# untitled.net
KiCad netlist of a schematic drawn in EAGLE
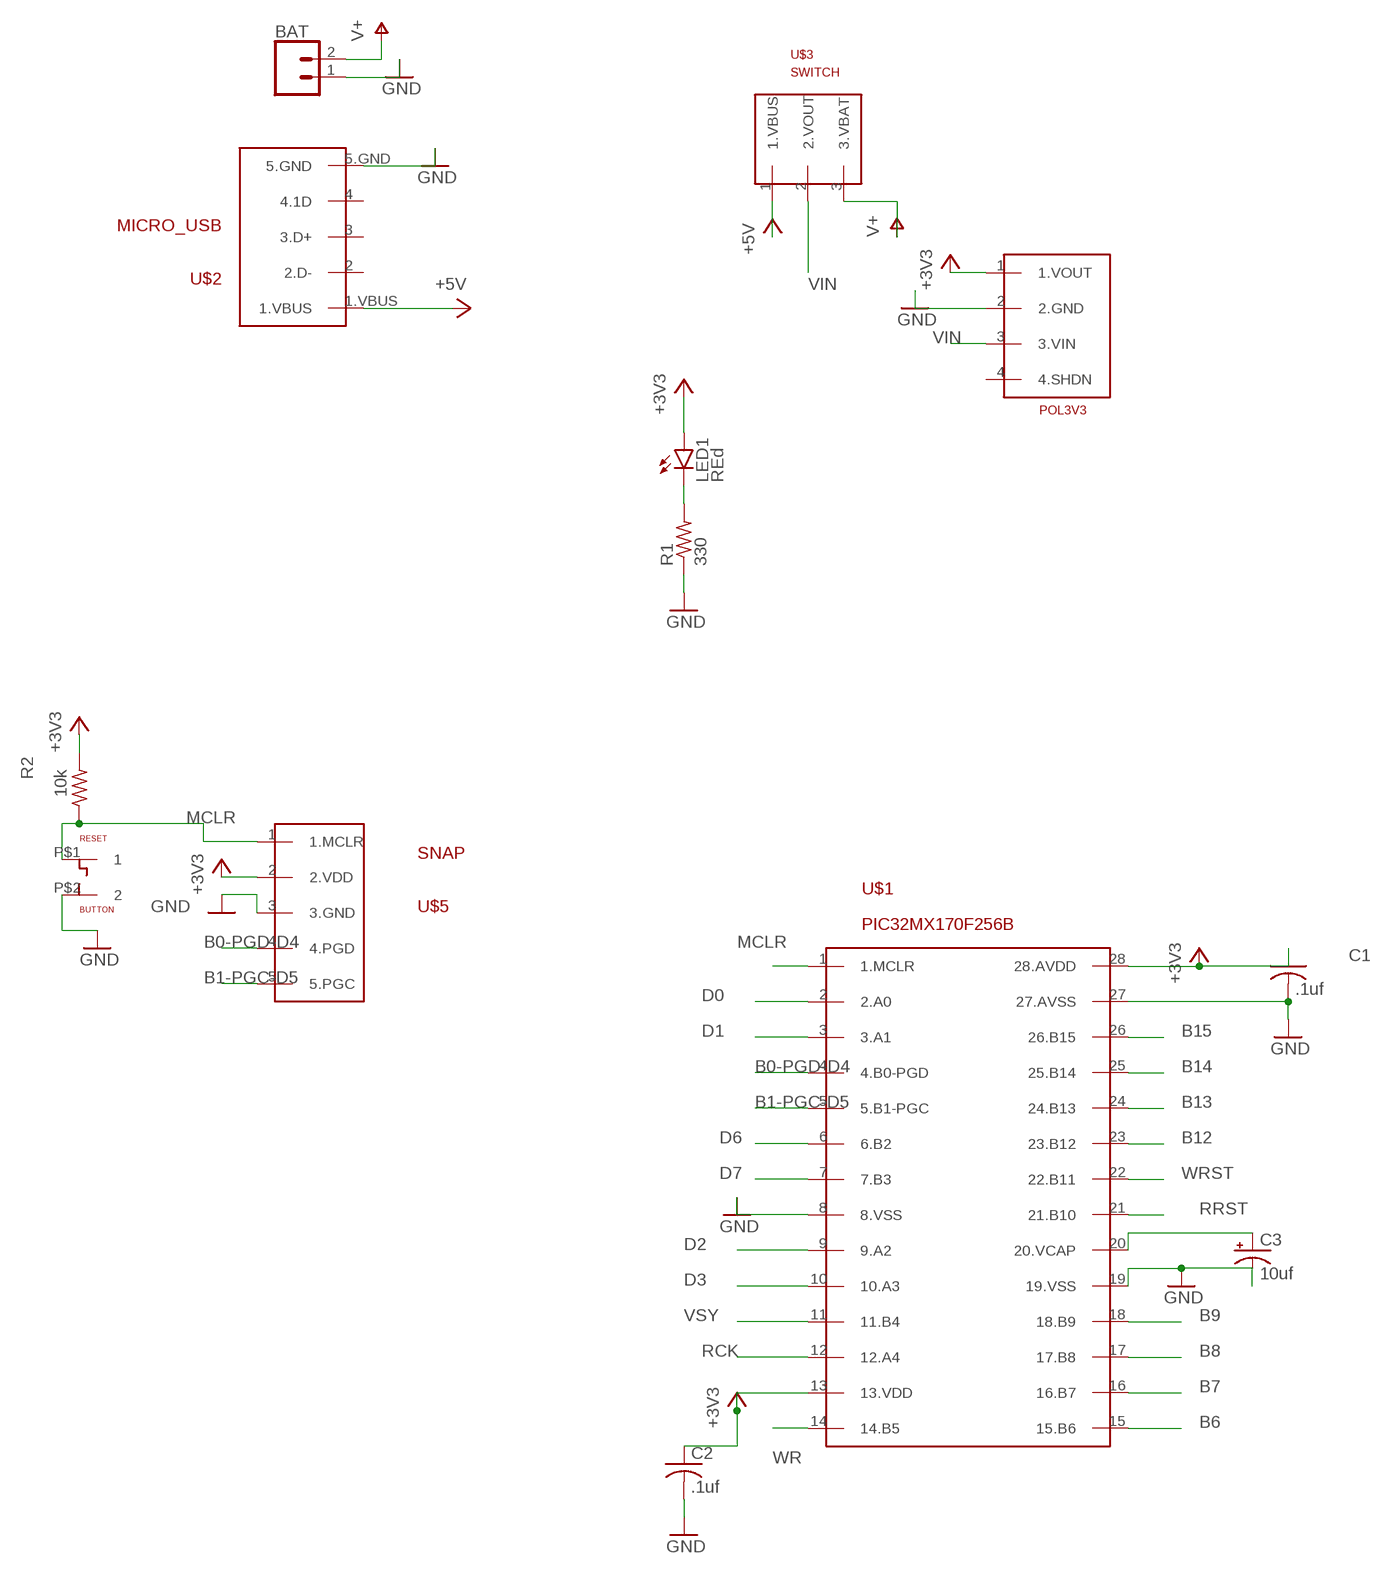
[diagram p0: schematic, sheet 1, part 1 of 2]
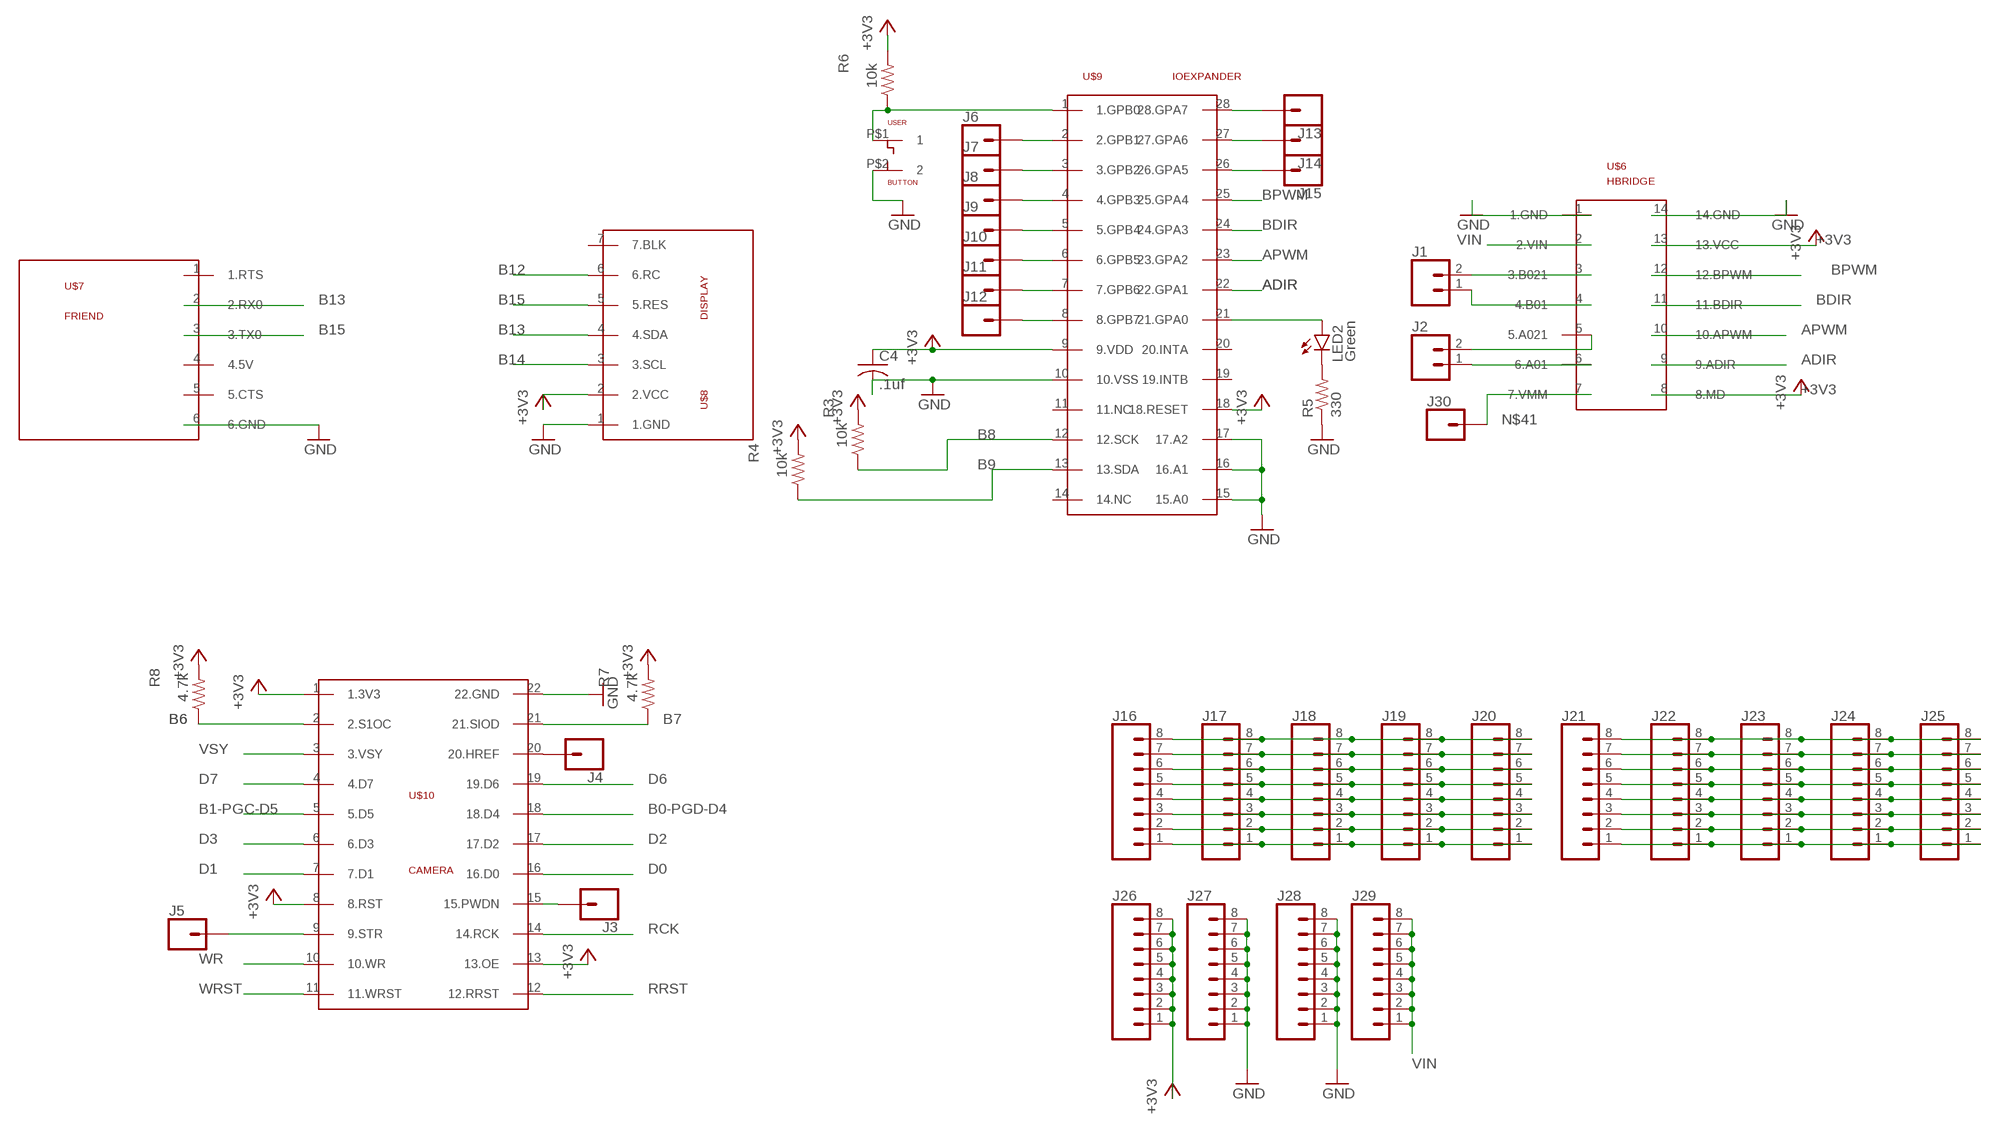
[diagram p1: schematic, sheet 1, part 2 of 2]

(export (version "E")
  (design (tool "Eeschema 10.0.6"))
  (components
    (comp (ref "BAT")
      (value "CONN_02")
      (footprint "eagle-import:1X02")
      (libsource (lib "eagle-import") (part "CONN_02"))
    )
    (comp (ref "C1")
      (value ".1uf")
      (footprint "eagle-import:C025-030X050")
      (libsource (lib "eagle-import") (part "C-US025-030X050"))
    )
    (comp (ref "C2")
      (value ".1uf")
      (footprint "eagle-import:C025-030X050")
      (libsource (lib "eagle-import") (part "C-US025-030X050"))
    )
    (comp (ref "C3")
      (value "10uf")
      (footprint "eagle-import:B45181B")
      (libsource (lib "eagle-import") (part "CPOL-USB45181B"))
    )
    (comp (ref "C4")
      (value ".1uf")
      (footprint "eagle-import:C025-030X050")
      (libsource (lib "eagle-import") (part "C-US025-030X050"))
    )
    (comp (ref "J1")
      (value "CONN_02")
      (footprint "eagle-import:1X02")
      (libsource (lib "eagle-import") (part "CONN_02"))
    )
    (comp (ref "J2")
      (value "CONN_02")
      (footprint "eagle-import:1X02")
      (libsource (lib "eagle-import") (part "CONN_02"))
    )
    (comp (ref "J3")
      (value "CONN_01")
      (footprint "eagle-import:1X01")
      (libsource (lib "eagle-import") (part "CONN_01"))
    )
    (comp (ref "J4")
      (value "CONN_01")
      (footprint "eagle-import:1X01")
      (libsource (lib "eagle-import") (part "CONN_01"))
    )
    (comp (ref "J5")
      (value "CONN_01")
      (footprint "eagle-import:1X01")
      (libsource (lib "eagle-import") (part "CONN_01"))
    )
    (comp (ref "J6")
      (value "CONN_01")
      (footprint "eagle-import:1X01")
      (libsource (lib "eagle-import") (part "CONN_01"))
    )
    (comp (ref "J7")
      (value "CONN_01")
      (footprint "eagle-import:1X01")
      (libsource (lib "eagle-import") (part "CONN_01"))
    )
    (comp (ref "J8")
      (value "CONN_01")
      (footprint "eagle-import:1X01")
      (libsource (lib "eagle-import") (part "CONN_01"))
    )
    (comp (ref "J9")
      (value "CONN_01")
      (footprint "eagle-import:1X01")
      (libsource (lib "eagle-import") (part "CONN_01"))
    )
    (comp (ref "J10")
      (value "CONN_01")
      (footprint "eagle-import:1X01")
      (libsource (lib "eagle-import") (part "CONN_01"))
    )
    (comp (ref "J11")
      (value "CONN_01")
      (footprint "eagle-import:1X01")
      (libsource (lib "eagle-import") (part "CONN_01"))
    )
    (comp (ref "J12")
      (value "CONN_01")
      (footprint "eagle-import:1X01")
      (libsource (lib "eagle-import") (part "CONN_01"))
    )
    (comp (ref "J13")
      (value "CONN_01")
      (footprint "eagle-import:1X01")
      (libsource (lib "eagle-import") (part "CONN_01"))
    )
    (comp (ref "J14")
      (value "CONN_01")
      (footprint "eagle-import:1X01")
      (libsource (lib "eagle-import") (part "CONN_01"))
    )
    (comp (ref "J15")
      (value "CONN_01")
      (footprint "eagle-import:1X01")
      (libsource (lib "eagle-import") (part "CONN_01"))
    )
    (comp (ref "J16")
      (value "CONN_08\"")
      (footprint "eagle-import:1X08")
      (libsource (lib "eagle-import") (part "CONN_08{dblquote}"))
    )
    (comp (ref "J17")
      (value "CONN_08\"")
      (footprint "eagle-import:1X08")
      (libsource (lib "eagle-import") (part "CONN_08{dblquote}"))
    )
    (comp (ref "J18")
      (value "CONN_08\"")
      (footprint "eagle-import:1X08")
      (libsource (lib "eagle-import") (part "CONN_08{dblquote}"))
    )
    (comp (ref "J19")
      (value "CONN_08\"")
      (footprint "eagle-import:1X08")
      (libsource (lib "eagle-import") (part "CONN_08{dblquote}"))
    )
    (comp (ref "J20")
      (value "CONN_08\"")
      (footprint "eagle-import:1X08")
      (libsource (lib "eagle-import") (part "CONN_08{dblquote}"))
    )
    (comp (ref "J21")
      (value "CONN_08\"")
      (footprint "eagle-import:1X08")
      (libsource (lib "eagle-import") (part "CONN_08{dblquote}"))
    )
    (comp (ref "J22")
      (value "CONN_08\"")
      (footprint "eagle-import:1X08")
      (libsource (lib "eagle-import") (part "CONN_08{dblquote}"))
    )
    (comp (ref "J23")
      (value "CONN_08\"")
      (footprint "eagle-import:1X08")
      (libsource (lib "eagle-import") (part "CONN_08{dblquote}"))
    )
    (comp (ref "J24")
      (value "CONN_08\"")
      (footprint "eagle-import:1X08")
      (libsource (lib "eagle-import") (part "CONN_08{dblquote}"))
    )
    (comp (ref "J25")
      (value "CONN_08\"")
      (footprint "eagle-import:1X08")
      (libsource (lib "eagle-import") (part "CONN_08{dblquote}"))
    )
    (comp (ref "J26")
      (value "CONN_08\"")
      (footprint "eagle-import:1X08")
      (libsource (lib "eagle-import") (part "CONN_08{dblquote}"))
    )
    (comp (ref "J27")
      (value "CONN_08\"")
      (footprint "eagle-import:1X08")
      (libsource (lib "eagle-import") (part "CONN_08{dblquote}"))
    )
    (comp (ref "J28")
      (value "CONN_08\"")
      (footprint "eagle-import:1X08")
      (libsource (lib "eagle-import") (part "CONN_08{dblquote}"))
    )
    (comp (ref "J29")
      (value "CONN_08\"")
      (footprint "eagle-import:1X08")
      (libsource (lib "eagle-import") (part "CONN_08{dblquote}"))
    )
    (comp (ref "J30")
      (value "CONN_01")
      (footprint "eagle-import:1X01")
      (libsource (lib "eagle-import") (part "CONN_01"))
    )
    (comp (ref "LED1")
      (value "REd")
      (footprint "eagle-import:LED3MM")
      (libsource (lib "eagle-import") (part "LED3MM"))
    )
    (comp (ref "LED2")
      (value "Green")
      (footprint "eagle-import:LED3MM")
      (libsource (lib "eagle-import") (part "LED3MM"))
    )
    (comp (ref "R1")
      (value "330")
      (footprint "eagle-import:0207_10")
      (libsource (lib "eagle-import") (part "R-US_0207/10"))
    )
    (comp (ref "R2")
      (value "10k")
      (footprint "eagle-import:0207_10")
      (libsource (lib "eagle-import") (part "R-US_0207/10"))
    )
    (comp (ref "R3")
      (value "10k")
      (footprint "eagle-import:0207_10")
      (libsource (lib "eagle-import") (part "R-US_0207/10"))
    )
    (comp (ref "R4")
      (value "10k")
      (footprint "eagle-import:0207_10")
      (libsource (lib "eagle-import") (part "R-US_0207/10"))
    )
    (comp (ref "R5")
      (value "330")
      (footprint "eagle-import:0207_10")
      (libsource (lib "eagle-import") (part "R-US_0207/10"))
    )
    (comp (ref "R6")
      (value "10k")
      (footprint "eagle-import:0207_10")
      (libsource (lib "eagle-import") (part "R-US_0207/10"))
    )
    (comp (ref "R7")
      (value "4.7k")
      (footprint "eagle-import:0207_10")
      (libsource (lib "eagle-import") (part "R-US_0207/10"))
    )
    (comp (ref "R8")
      (value "4.7k")
      (footprint "eagle-import:0207_10")
      (libsource (lib "eagle-import") (part "R-US_0207/10"))
    )
    (comp (ref "RESET")
      (value "BUTTON")
      (footprint "eagle-import:BUTTON")
      (libsource (lib "eagle-import") (part "BUTTON"))
    )
    (comp (ref "U$1")
      (value "PIC32MX170F256B")
      (footprint "eagle-import:DIL28-3")
      (libsource (lib "eagle-import") (part "PIC32MX170F256B"))
    )
    (comp (ref "U$2")
      (value "MICRO_USB")
      (footprint "eagle-import:MICRO_USB")
      (libsource (lib "eagle-import") (part "MICRO_USB"))
    )
    (comp (ref "U$3")
      (value "SWITCH")
      (footprint "eagle-import:SLIDE")
      (libsource (lib "eagle-import") (part "SWITCH"))
    )
    (comp (ref "U$4")
      (value "POL3V3")
      (footprint "eagle-import:POL3V3")
      (libsource (lib "eagle-import") (part "POL3V3"))
    )
    (comp (ref "U$5")
      (value "SNAP")
      (footprint "eagle-import:SNAP")
      (libsource (lib "eagle-import") (part "SNAP"))
    )
    (comp (ref "U$6")
      (value "HBRIDGE")
      (footprint "eagle-import:HBRIDGE")
      (libsource (lib "eagle-import") (part "HBRIDGE"))
    )
    (comp (ref "U$7")
      (value "FRIEND")
      (footprint "eagle-import:FRIEND")
      (libsource (lib "eagle-import") (part "FRIEND"))
    )
    (comp (ref "U$8")
      (value "DISPLAY")
      (footprint "eagle-import:DISPLAY")
      (libsource (lib "eagle-import") (part "DISPLAY"))
    )
    (comp (ref "U$9")
      (value "IOEXPANDER")
      (footprint "eagle-import:DIL28-3")
      (libsource (lib "eagle-import") (part "IOEXPANDER"))
    )
    (comp (ref "U$10")
      (value "CAMERA")
      (footprint "eagle-import:CAMERA")
      (libsource (lib "eagle-import") (part "CAMERA"))
    )
    (comp (ref "USER")
      (value "BUTTON")
      (footprint "eagle-import:BUTTON")
      (libsource (lib "eagle-import") (part "BUTTON"))
    )
  )
  (nets
    (net (code "1") (name "+3V3") (class "Default")
      (node (ref "C1") (pin "1") (pinfunction "1_1") (pintype "passive"))
      (node (ref "C2") (pin "1") (pinfunction "1_1") (pintype "passive"))
      (node (ref "C4") (pin "1") (pinfunction "1_1") (pintype "passive"))
      (node (ref "J26") (pin "1") (pinfunction "1_1") (pintype "passive"))
      (node (ref "J26") (pin "2") (pinfunction "2_2") (pintype "passive"))
      (node (ref "J26") (pin "3") (pinfunction "3_3") (pintype "passive"))
      (node (ref "J26") (pin "4") (pinfunction "4_4") (pintype "passive"))
      (node (ref "J26") (pin "5") (pinfunction "5_5") (pintype "passive"))
      (node (ref "J26") (pin "6") (pinfunction "6_6") (pintype "passive"))
      (node (ref "J26") (pin "7") (pinfunction "7_7") (pintype "passive"))
      (node (ref "J26") (pin "8") (pinfunction "8_8") (pintype "passive"))
      (node (ref "LED1") (pin "A") (pinfunction "A_A") (pintype "passive"))
      (node (ref "R2") (pin "2") (pinfunction "2_2") (pintype "passive"))
      (node (ref "R3") (pin "2") (pinfunction "2_2") (pintype "passive"))
      (node (ref "R4") (pin "2") (pinfunction "2_2") (pintype "passive"))
      (node (ref "R6") (pin "2") (pinfunction "2_2") (pintype "passive"))
      (node (ref "R7") (pin "2") (pinfunction "2_2") (pintype "passive"))
      (node (ref "R8") (pin "2") (pinfunction "2_2") (pintype "passive"))
      (node (ref "U$1") (pin "13") (pinfunction "13.VDD_13") (pintype "bidirectional"))
      (node (ref "U$1") (pin "28") (pinfunction "28.AVDD_28") (pintype "bidirectional"))
      (node (ref "U$10") (pin "1") (pinfunction "1.3V3_1") (pintype "bidirectional"))
      (node (ref "U$10") (pin "13") (pinfunction "13.OE_13") (pintype "bidirectional"))
      (node (ref "U$10") (pin "8") (pinfunction "8.RST_8") (pintype "bidirectional"))
      (node (ref "U$4") (pin "1") (pinfunction "1.VOUT_1") (pintype "bidirectional"))
      (node (ref "U$5") (pin "2") (pinfunction "2.VDD_2") (pintype "bidirectional"))
      (node (ref "U$6") (pin "13") (pinfunction "13.VCC_13") (pintype "bidirectional"))
      (node (ref "U$6") (pin "8") (pinfunction "8.MD_8") (pintype "bidirectional"))
      (node (ref "U$8") (pin "2") (pinfunction "2.VCC_2") (pintype "bidirectional"))
      (node (ref "U$9") (pin "18") (pinfunction "18.RESET_18") (pintype "bidirectional"))
      (node (ref "U$9") (pin "9") (pinfunction "9.VDD_9") (pintype "bidirectional"))
    )
    (net (code "2") (name "+5V") (class "Default")
      (node (ref "U$2") (pin "1.VBUS") (pinfunction "1.VBUS_1.VBUS") (pintype "bidirectional"))
      (node (ref "U$3") (pin "1") (pinfunction "1.VBUS_1") (pintype "bidirectional"))
    )
    (net (code "3") (name "/ADIR") (class "Default")
      (node (ref "U$6") (pin "9") (pinfunction "9.ADIR_9") (pintype "bidirectional"))
      (node (ref "U$9") (pin "22") (pinfunction "22.GPA1_22") (pintype "bidirectional"))
    )
    (net (code "4") (name "/APWM") (class "Default")
      (node (ref "U$6") (pin "10") (pinfunction "10.APWM_10") (pintype "bidirectional"))
      (node (ref "U$9") (pin "23") (pinfunction "23.GPA2_23") (pintype "bidirectional"))
    )
    (net (code "5") (name "/B0-PGD-D4") (class "Default")
      (node (ref "U$1") (pin "4") (pinfunction "4.B0-PGD_4") (pintype "bidirectional"))
      (node (ref "U$10") (pin "18") (pinfunction "18.D4_18") (pintype "bidirectional"))
      (node (ref "U$5") (pin "4") (pinfunction "4.PGD_4") (pintype "bidirectional"))
    )
    (net (code "6") (name "/B1-PGC-D5") (class "Default")
      (node (ref "U$1") (pin "5") (pinfunction "5.B1-PGC_5") (pintype "bidirectional"))
      (node (ref "U$10") (pin "5") (pinfunction "5.D5_5") (pintype "bidirectional"))
      (node (ref "U$5") (pin "5") (pinfunction "5.PGC_5") (pintype "bidirectional"))
    )
    (net (code "7") (name "/B6") (class "Default")
      (node (ref "R8") (pin "1") (pinfunction "1_1") (pintype "passive"))
      (node (ref "U$1") (pin "15") (pinfunction "15.B6_15") (pintype "bidirectional"))
      (node (ref "U$10") (pin "2") (pinfunction "2.S1OC_2") (pintype "bidirectional"))
    )
    (net (code "8") (name "/B7") (class "Default")
      (node (ref "R7") (pin "1") (pinfunction "1_1") (pintype "passive"))
      (node (ref "U$1") (pin "16") (pinfunction "16.B7_16") (pintype "bidirectional"))
      (node (ref "U$10") (pin "21") (pinfunction "21.SIOD_21") (pintype "bidirectional"))
    )
    (net (code "9") (name "/B8") (class "Default")
      (node (ref "R3") (pin "1") (pinfunction "1_1") (pintype "passive"))
      (node (ref "U$1") (pin "17") (pinfunction "17.B8_17") (pintype "bidirectional"))
      (node (ref "U$9") (pin "12") (pinfunction "12.SCK_12") (pintype "bidirectional"))
    )
    (net (code "10") (name "/B9") (class "Default")
      (node (ref "R4") (pin "1") (pinfunction "1_1") (pintype "passive"))
      (node (ref "U$1") (pin "18") (pinfunction "18.B9_18") (pintype "bidirectional"))
      (node (ref "U$9") (pin "13") (pinfunction "13.SDA_13") (pintype "bidirectional"))
    )
    (net (code "11") (name "/B12") (class "Default")
      (node (ref "U$1") (pin "23") (pinfunction "23.B12_23") (pintype "bidirectional"))
      (node (ref "U$8") (pin "6") (pinfunction "6.RC_6") (pintype "bidirectional"))
    )
    (net (code "12") (name "/B13") (class "Default")
      (node (ref "U$1") (pin "24") (pinfunction "24.B13_24") (pintype "bidirectional"))
      (node (ref "U$7") (pin "2") (pinfunction "2.RX0_2") (pintype "bidirectional"))
      (node (ref "U$8") (pin "4") (pinfunction "4.SDA_4") (pintype "bidirectional"))
    )
    (net (code "13") (name "/B14") (class "Default")
      (node (ref "U$1") (pin "25") (pinfunction "25.B14_25") (pintype "bidirectional"))
      (node (ref "U$8") (pin "3") (pinfunction "3.SCL_3") (pintype "bidirectional"))
    )
    (net (code "14") (name "/B15") (class "Default")
      (node (ref "U$1") (pin "26") (pinfunction "26.B15_26") (pintype "bidirectional"))
      (node (ref "U$7") (pin "3") (pinfunction "3.TX0_3") (pintype "bidirectional"))
      (node (ref "U$8") (pin "5") (pinfunction "5.RES_5") (pintype "bidirectional"))
    )
    (net (code "15") (name "/BDIR") (class "Default")
      (node (ref "U$6") (pin "11") (pinfunction "11.BDIR_11") (pintype "bidirectional"))
      (node (ref "U$9") (pin "24") (pinfunction "24.GPA3_24") (pintype "bidirectional"))
    )
    (net (code "16") (name "/BPWM") (class "Default")
      (node (ref "U$6") (pin "12") (pinfunction "12.BPWM_12") (pintype "bidirectional"))
      (node (ref "U$9") (pin "25") (pinfunction "25.GPA4_25") (pintype "bidirectional"))
    )
    (net (code "17") (name "/D0") (class "Default")
      (node (ref "U$1") (pin "2") (pinfunction "2.A0_2") (pintype "bidirectional"))
      (node (ref "U$10") (pin "16") (pinfunction "16.D0_16") (pintype "bidirectional"))
    )
    (net (code "18") (name "/D1") (class "Default")
      (node (ref "U$1") (pin "3") (pinfunction "3.A1_3") (pintype "bidirectional"))
      (node (ref "U$10") (pin "7") (pinfunction "7.D1_7") (pintype "bidirectional"))
    )
    (net (code "19") (name "/D2") (class "Default")
      (node (ref "U$1") (pin "9") (pinfunction "9.A2_9") (pintype "bidirectional"))
      (node (ref "U$10") (pin "17") (pinfunction "17.D2_17") (pintype "bidirectional"))
    )
    (net (code "20") (name "/D3") (class "Default")
      (node (ref "U$1") (pin "10") (pinfunction "10.A3_10") (pintype "bidirectional"))
      (node (ref "U$10") (pin "6") (pinfunction "6.D3_6") (pintype "bidirectional"))
    )
    (net (code "21") (name "/D6") (class "Default")
      (node (ref "U$1") (pin "6") (pinfunction "6.B2_6") (pintype "bidirectional"))
      (node (ref "U$10") (pin "19") (pinfunction "19.D6_19") (pintype "bidirectional"))
    )
    (net (code "22") (name "/D7") (class "Default")
      (node (ref "U$1") (pin "7") (pinfunction "7.B3_7") (pintype "bidirectional"))
      (node (ref "U$10") (pin "4") (pinfunction "4.D7_4") (pintype "bidirectional"))
    )
    (net (code "23") (name "/MCLR") (class "Default")
      (node (ref "R2") (pin "1") (pinfunction "1_1") (pintype "passive"))
      (node (ref "RESET") (pin "P$1") (pinfunction "1_P$1") (pintype "bidirectional"))
      (node (ref "U$1") (pin "1") (pinfunction "1.MCLR_1") (pintype "bidirectional"))
      (node (ref "U$5") (pin "1") (pinfunction "1.MCLR_1") (pintype "bidirectional"))
    )
    (net (code "24") (name "/N$41") (class "Default")
      (node (ref "J30") (pin "1") (pinfunction "1_1") (pintype "passive"))
      (node (ref "U$6") (pin "7") (pinfunction "7.VMM_7") (pintype "bidirectional"))
    )
    (net (code "25") (name "/RCK") (class "Default")
      (node (ref "U$1") (pin "12") (pinfunction "12.A4_12") (pintype "bidirectional"))
      (node (ref "U$10") (pin "14") (pinfunction "14.RCK_14") (pintype "bidirectional"))
    )
    (net (code "26") (name "/RRST") (class "Default")
      (node (ref "U$1") (pin "21") (pinfunction "21.B10_21") (pintype "bidirectional"))
      (node (ref "U$10") (pin "12") (pinfunction "12.RRST_12") (pintype "bidirectional"))
    )
    (net (code "27") (name "/VIN") (class "Default")
      (node (ref "J29") (pin "1") (pinfunction "1_1") (pintype "passive"))
      (node (ref "J29") (pin "2") (pinfunction "2_2") (pintype "passive"))
      (node (ref "J29") (pin "3") (pinfunction "3_3") (pintype "passive"))
      (node (ref "J29") (pin "4") (pinfunction "4_4") (pintype "passive"))
      (node (ref "J29") (pin "5") (pinfunction "5_5") (pintype "passive"))
      (node (ref "J29") (pin "6") (pinfunction "6_6") (pintype "passive"))
      (node (ref "J29") (pin "7") (pinfunction "7_7") (pintype "passive"))
      (node (ref "J29") (pin "8") (pinfunction "8_8") (pintype "passive"))
      (node (ref "U$3") (pin "2") (pinfunction "2.VOUT_2") (pintype "bidirectional"))
      (node (ref "U$4") (pin "3") (pinfunction "3.VIN_3") (pintype "bidirectional"))
      (node (ref "U$6") (pin "2") (pinfunction "2.VIN_2") (pintype "bidirectional"))
    )
    (net (code "28") (name "/VSY") (class "Default")
      (node (ref "U$1") (pin "11") (pinfunction "11.B4_11") (pintype "bidirectional"))
      (node (ref "U$10") (pin "3") (pinfunction "3.VSY_3") (pintype "bidirectional"))
    )
    (net (code "29") (name "/WR") (class "Default")
      (node (ref "U$1") (pin "14") (pinfunction "14.B5_14") (pintype "bidirectional"))
      (node (ref "U$10") (pin "10") (pinfunction "10.WR_10") (pintype "bidirectional"))
    )
    (net (code "30") (name "/WRST") (class "Default")
      (node (ref "U$1") (pin "22") (pinfunction "22.B11_22") (pintype "bidirectional"))
      (node (ref "U$10") (pin "11") (pinfunction "11.WRST_11") (pintype "bidirectional"))
    )
    (net (code "31") (name "GND") (class "Default")
      (node (ref "BAT") (pin "1") (pinfunction "1_1") (pintype "passive"))
      (node (ref "C1") (pin "2") (pinfunction "2_2") (pintype "passive"))
      (node (ref "C2") (pin "2") (pinfunction "2_2") (pintype "passive"))
      (node (ref "C3") (pin "-") (pinfunction "-_-") (pintype "passive"))
      (node (ref "C4") (pin "2") (pinfunction "2_2") (pintype "passive"))
      (node (ref "J27") (pin "1") (pinfunction "1_1") (pintype "passive"))
      (node (ref "J27") (pin "2") (pinfunction "2_2") (pintype "passive"))
      (node (ref "J27") (pin "3") (pinfunction "3_3") (pintype "passive"))
      (node (ref "J27") (pin "4") (pinfunction "4_4") (pintype "passive"))
      (node (ref "J27") (pin "5") (pinfunction "5_5") (pintype "passive"))
      (node (ref "J27") (pin "6") (pinfunction "6_6") (pintype "passive"))
      (node (ref "J27") (pin "7") (pinfunction "7_7") (pintype "passive"))
      (node (ref "J27") (pin "8") (pinfunction "8_8") (pintype "passive"))
      (node (ref "J28") (pin "1") (pinfunction "1_1") (pintype "passive"))
      (node (ref "J28") (pin "2") (pinfunction "2_2") (pintype "passive"))
      (node (ref "J28") (pin "3") (pinfunction "3_3") (pintype "passive"))
      (node (ref "J28") (pin "4") (pinfunction "4_4") (pintype "passive"))
      (node (ref "J28") (pin "5") (pinfunction "5_5") (pintype "passive"))
      (node (ref "J28") (pin "6") (pinfunction "6_6") (pintype "passive"))
      (node (ref "J28") (pin "7") (pinfunction "7_7") (pintype "passive"))
      (node (ref "J28") (pin "8") (pinfunction "8_8") (pintype "passive"))
      (node (ref "R1") (pin "1") (pinfunction "1_1") (pintype "passive"))
      (node (ref "R5") (pin "1") (pinfunction "1_1") (pintype "passive"))
      (node (ref "RESET") (pin "P$2") (pinfunction "2_P$2") (pintype "bidirectional"))
      (node (ref "U$1") (pin "19") (pinfunction "19.VSS_19") (pintype "bidirectional"))
      (node (ref "U$1") (pin "27") (pinfunction "27.AVSS_27") (pintype "bidirectional"))
      (node (ref "U$1") (pin "8") (pinfunction "8.VSS_8") (pintype "bidirectional"))
      (node (ref "U$10") (pin "22") (pinfunction "22.GND_22") (pintype "bidirectional"))
      (node (ref "U$2") (pin "5.GND") (pinfunction "5.GND_5.GND") (pintype "bidirectional"))
      (node (ref "U$4") (pin "2") (pinfunction "2.GND_2") (pintype "bidirectional"))
      (node (ref "U$5") (pin "3") (pinfunction "3.GND_3") (pintype "bidirectional"))
      (node (ref "U$6") (pin "1") (pinfunction "1.GND_1") (pintype "bidirectional"))
      (node (ref "U$6") (pin "14") (pinfunction "14.GND_14") (pintype "bidirectional"))
      (node (ref "U$7") (pin "6") (pinfunction "6.GND_6") (pintype "bidirectional"))
      (node (ref "U$8") (pin "1") (pinfunction "1.GND_1") (pintype "bidirectional"))
      (node (ref "U$9") (pin "10") (pinfunction "10.VSS_10") (pintype "bidirectional"))
      (node (ref "U$9") (pin "15") (pinfunction "15.A0_15") (pintype "bidirectional"))
      (node (ref "U$9") (pin "16") (pinfunction "16.A1_16") (pintype "bidirectional"))
      (node (ref "U$9") (pin "17") (pinfunction "17.A2_17") (pintype "bidirectional"))
      (node (ref "USER") (pin "P$2") (pinfunction "2_P$2") (pintype "bidirectional"))
    )
    (net (code "32") (name "Net-(J16-Pad1)") (class "Default")
      (node (ref "J16") (pin "1") (pinfunction "1_1") (pintype "passive"))
      (node (ref "J17") (pin "1") (pinfunction "1_1") (pintype "passive"))
      (node (ref "J18") (pin "1") (pinfunction "1_1") (pintype "passive"))
      (node (ref "J19") (pin "1") (pinfunction "1_1") (pintype "passive"))
      (node (ref "J20") (pin "1") (pinfunction "1_1") (pintype "passive"))
    )
    (net (code "33") (name "Net-(J16-Pad2)") (class "Default")
      (node (ref "J16") (pin "2") (pinfunction "2_2") (pintype "passive"))
      (node (ref "J17") (pin "2") (pinfunction "2_2") (pintype "passive"))
      (node (ref "J18") (pin "2") (pinfunction "2_2") (pintype "passive"))
      (node (ref "J19") (pin "2") (pinfunction "2_2") (pintype "passive"))
      (node (ref "J20") (pin "2") (pinfunction "2_2") (pintype "passive"))
    )
    (net (code "34") (name "Net-(J16-Pad3)") (class "Default")
      (node (ref "J16") (pin "3") (pinfunction "3_3") (pintype "passive"))
      (node (ref "J17") (pin "3") (pinfunction "3_3") (pintype "passive"))
      (node (ref "J18") (pin "3") (pinfunction "3_3") (pintype "passive"))
      (node (ref "J19") (pin "3") (pinfunction "3_3") (pintype "passive"))
      (node (ref "J20") (pin "3") (pinfunction "3_3") (pintype "passive"))
    )
    (net (code "35") (name "Net-(J16-Pad4)") (class "Default")
      (node (ref "J16") (pin "4") (pinfunction "4_4") (pintype "passive"))
      (node (ref "J17") (pin "4") (pinfunction "4_4") (pintype "passive"))
      (node (ref "J18") (pin "4") (pinfunction "4_4") (pintype "passive"))
      (node (ref "J19") (pin "4") (pinfunction "4_4") (pintype "passive"))
      (node (ref "J20") (pin "4") (pinfunction "4_4") (pintype "passive"))
    )
    (net (code "36") (name "Net-(J16-Pad5)") (class "Default")
      (node (ref "J16") (pin "5") (pinfunction "5_5") (pintype "passive"))
      (node (ref "J17") (pin "5") (pinfunction "5_5") (pintype "passive"))
      (node (ref "J18") (pin "5") (pinfunction "5_5") (pintype "passive"))
      (node (ref "J19") (pin "5") (pinfunction "5_5") (pintype "passive"))
      (node (ref "J20") (pin "5") (pinfunction "5_5") (pintype "passive"))
    )
    (net (code "37") (name "Net-(J16-Pad6)") (class "Default")
      (node (ref "J16") (pin "6") (pinfunction "6_6") (pintype "passive"))
      (node (ref "J17") (pin "6") (pinfunction "6_6") (pintype "passive"))
      (node (ref "J18") (pin "6") (pinfunction "6_6") (pintype "passive"))
      (node (ref "J19") (pin "6") (pinfunction "6_6") (pintype "passive"))
      (node (ref "J20") (pin "6") (pinfunction "6_6") (pintype "passive"))
    )
    (net (code "38") (name "Net-(J16-Pad7)") (class "Default")
      (node (ref "J16") (pin "7") (pinfunction "7_7") (pintype "passive"))
      (node (ref "J17") (pin "7") (pinfunction "7_7") (pintype "passive"))
      (node (ref "J18") (pin "7") (pinfunction "7_7") (pintype "passive"))
      (node (ref "J19") (pin "7") (pinfunction "7_7") (pintype "passive"))
      (node (ref "J20") (pin "7") (pinfunction "7_7") (pintype "passive"))
    )
    (net (code "39") (name "Net-(J16-Pad8)") (class "Default")
      (node (ref "J16") (pin "8") (pinfunction "8_8") (pintype "passive"))
      (node (ref "J17") (pin "8") (pinfunction "8_8") (pintype "passive"))
      (node (ref "J18") (pin "8") (pinfunction "8_8") (pintype "passive"))
      (node (ref "J19") (pin "8") (pinfunction "8_8") (pintype "passive"))
      (node (ref "J20") (pin "8") (pinfunction "8_8") (pintype "passive"))
    )
    (net (code "40") (name "Net-(J21-Pad1)") (class "Default")
      (node (ref "J21") (pin "1") (pinfunction "1_1") (pintype "passive"))
      (node (ref "J22") (pin "1") (pinfunction "1_1") (pintype "passive"))
      (node (ref "J23") (pin "1") (pinfunction "1_1") (pintype "passive"))
      (node (ref "J24") (pin "1") (pinfunction "1_1") (pintype "passive"))
      (node (ref "J25") (pin "1") (pinfunction "1_1") (pintype "passive"))
    )
    (net (code "41") (name "Net-(J21-Pad2)") (class "Default")
      (node (ref "J21") (pin "2") (pinfunction "2_2") (pintype "passive"))
      (node (ref "J22") (pin "2") (pinfunction "2_2") (pintype "passive"))
      (node (ref "J23") (pin "2") (pinfunction "2_2") (pintype "passive"))
      (node (ref "J24") (pin "2") (pinfunction "2_2") (pintype "passive"))
      (node (ref "J25") (pin "2") (pinfunction "2_2") (pintype "passive"))
    )
    (net (code "42") (name "Net-(J21-Pad3)") (class "Default")
      (node (ref "J21") (pin "3") (pinfunction "3_3") (pintype "passive"))
      (node (ref "J22") (pin "3") (pinfunction "3_3") (pintype "passive"))
      (node (ref "J23") (pin "3") (pinfunction "3_3") (pintype "passive"))
      (node (ref "J24") (pin "3") (pinfunction "3_3") (pintype "passive"))
      (node (ref "J25") (pin "3") (pinfunction "3_3") (pintype "passive"))
    )
    (net (code "43") (name "Net-(J21-Pad4)") (class "Default")
      (node (ref "J21") (pin "4") (pinfunction "4_4") (pintype "passive"))
      (node (ref "J22") (pin "4") (pinfunction "4_4") (pintype "passive"))
      (node (ref "J23") (pin "4") (pinfunction "4_4") (pintype "passive"))
      (node (ref "J24") (pin "4") (pinfunction "4_4") (pintype "passive"))
      (node (ref "J25") (pin "4") (pinfunction "4_4") (pintype "passive"))
    )
    (net (code "44") (name "Net-(J21-Pad5)") (class "Default")
      (node (ref "J21") (pin "5") (pinfunction "5_5") (pintype "passive"))
      (node (ref "J22") (pin "5") (pinfunction "5_5") (pintype "passive"))
      (node (ref "J23") (pin "5") (pinfunction "5_5") (pintype "passive"))
      (node (ref "J24") (pin "5") (pinfunction "5_5") (pintype "passive"))
      (node (ref "J25") (pin "5") (pinfunction "5_5") (pintype "passive"))
    )
    (net (code "45") (name "Net-(J21-Pad6)") (class "Default")
      (node (ref "J21") (pin "6") (pinfunction "6_6") (pintype "passive"))
      (node (ref "J22") (pin "6") (pinfunction "6_6") (pintype "passive"))
      (node (ref "J23") (pin "6") (pinfunction "6_6") (pintype "passive"))
      (node (ref "J24") (pin "6") (pinfunction "6_6") (pintype "passive"))
      (node (ref "J25") (pin "6") (pinfunction "6_6") (pintype "passive"))
    )
    (net (code "46") (name "Net-(J21-Pad7)") (class "Default")
      (node (ref "J21") (pin "7") (pinfunction "7_7") (pintype "passive"))
      (node (ref "J22") (pin "7") (pinfunction "7_7") (pintype "passive"))
      (node (ref "J23") (pin "7") (pinfunction "7_7") (pintype "passive"))
      (node (ref "J24") (pin "7") (pinfunction "7_7") (pintype "passive"))
      (node (ref "J25") (pin "7") (pinfunction "7_7") (pintype "passive"))
    )
    (net (code "47") (name "Net-(J21-Pad8)") (class "Default")
      (node (ref "J21") (pin "8") (pinfunction "8_8") (pintype "passive"))
      (node (ref "J22") (pin "8") (pinfunction "8_8") (pintype "passive"))
      (node (ref "J23") (pin "8") (pinfunction "8_8") (pintype "passive"))
      (node (ref "J24") (pin "8") (pinfunction "8_8") (pintype "passive"))
      (node (ref "J25") (pin "8") (pinfunction "8_8") (pintype "passive"))
    )
    (net (code "48") (name "Net-(LED1-C)") (class "Default")
      (node (ref "LED1") (pin "K") (pinfunction "C_K") (pintype "passive"))
      (node (ref "R1") (pin "2") (pinfunction "2_2") (pintype "passive"))
    )
    (net (code "49") (name "Net-(LED2-C)") (class "Default")
      (node (ref "LED2") (pin "K") (pinfunction "C_K") (pintype "passive"))
      (node (ref "R5") (pin "2") (pinfunction "2_2") (pintype "passive"))
    )
    (net (code "50") (name "Net-(U$1-20.VCAP)") (class "Default")
      (node (ref "C3") (pin "+") (pinfunction "+_+") (pintype "passive"))
      (node (ref "U$1") (pin "20") (pinfunction "20.VCAP_20") (pintype "bidirectional"))
    )
    (net (code "51") (name "Net-(U$6-3.B021)") (class "Default")
      (node (ref "J1") (pin "2") (pinfunction "2_2") (pintype "passive"))
      (node (ref "U$6") (pin "3") (pinfunction "3.B021_3") (pintype "bidirectional"))
    )
    (net (code "52") (name "Net-(U$6-4.B01)") (class "Default")
      (node (ref "J1") (pin "1") (pinfunction "1_1") (pintype "passive"))
      (node (ref "U$6") (pin "4") (pinfunction "4.B01_4") (pintype "bidirectional"))
    )
    (net (code "53") (name "Net-(U$6-5.A021)") (class "Default")
      (node (ref "J2") (pin "2") (pinfunction "2_2") (pintype "passive"))
      (node (ref "U$6") (pin "5") (pinfunction "5.A021_5") (pintype "bidirectional"))
    )
    (net (code "54") (name "Net-(U$6-6.A01)") (class "Default")
      (node (ref "J2") (pin "1") (pinfunction "1_1") (pintype "passive"))
      (node (ref "U$6") (pin "6") (pinfunction "6.A01_6") (pintype "bidirectional"))
    )
    (net (code "55") (name "Net-(U$9-1.GPB0)") (class "Default")
      (node (ref "R6") (pin "1") (pinfunction "1_1") (pintype "passive"))
      (node (ref "U$9") (pin "1") (pinfunction "1.GPB0_1") (pintype "bidirectional"))
      (node (ref "USER") (pin "P$1") (pinfunction "1_P$1") (pintype "bidirectional"))
    )
    (net (code "56") (name "Net-(U$9-2.GPB1)") (class "Default")
      (node (ref "J6") (pin "1") (pinfunction "1_1") (pintype "passive"))
      (node (ref "U$9") (pin "2") (pinfunction "2.GPB1_2") (pintype "bidirectional"))
    )
    (net (code "57") (name "Net-(U$9-3.GPB2)") (class "Default")
      (node (ref "J7") (pin "1") (pinfunction "1_1") (pintype "passive"))
      (node (ref "U$9") (pin "3") (pinfunction "3.GPB2_3") (pintype "bidirectional"))
    )
    (net (code "58") (name "Net-(U$9-4.GPB3)") (class "Default")
      (node (ref "J8") (pin "1") (pinfunction "1_1") (pintype "passive"))
      (node (ref "U$9") (pin "4") (pinfunction "4.GPB3_4") (pintype "bidirectional"))
    )
    (net (code "59") (name "Net-(U$9-5.GPB4)") (class "Default")
      (node (ref "J9") (pin "1") (pinfunction "1_1") (pintype "passive"))
      (node (ref "U$9") (pin "5") (pinfunction "5.GPB4_5") (pintype "bidirectional"))
    )
    (net (code "60") (name "Net-(U$9-6.GPB5)") (class "Default")
      (node (ref "J10") (pin "1") (pinfunction "1_1") (pintype "passive"))
      (node (ref "U$9") (pin "6") (pinfunction "6.GPB5_6") (pintype "bidirectional"))
    )
    (net (code "61") (name "Net-(U$9-7.GPB6)") (class "Default")
      (node (ref "J11") (pin "1") (pinfunction "1_1") (pintype "passive"))
      (node (ref "U$9") (pin "7") (pinfunction "7.GPB6_7") (pintype "bidirectional"))
    )
    (net (code "62") (name "Net-(U$9-8.GPB7)") (class "Default")
      (node (ref "J12") (pin "1") (pinfunction "1_1") (pintype "passive"))
      (node (ref "U$9") (pin "8") (pinfunction "8.GPB7_8") (pintype "bidirectional"))
    )
    (net (code "63") (name "Net-(U$9-21.GPA0)") (class "Default")
      (node (ref "LED2") (pin "A") (pinfunction "A_A") (pintype "passive"))
      (node (ref "U$9") (pin "21") (pinfunction "21.GPA0_21") (pintype "bidirectional"))
    )
    (net (code "64") (name "Net-(U$9-26.GPA5)") (class "Default")
      (node (ref "J15") (pin "1") (pinfunction "1_1") (pintype "passive"))
      (node (ref "U$9") (pin "26") (pinfunction "26.GPA5_26") (pintype "bidirectional"))
    )
    (net (code "65") (name "Net-(U$9-27.GPA6)") (class "Default")
      (node (ref "J14") (pin "1") (pinfunction "1_1") (pintype "passive"))
      (node (ref "U$9") (pin "27") (pinfunction "27.GPA6_27") (pintype "bidirectional"))
    )
    (net (code "66") (name "Net-(U$9-28.GPA7)") (class "Default")
      (node (ref "J13") (pin "1") (pinfunction "1_1") (pintype "passive"))
      (node (ref "U$9") (pin "28") (pinfunction "28.GPA7_28") (pintype "bidirectional"))
    )
    (net (code "67") (name "Net-(U$10-9.STR)") (class "Default")
      (node (ref "J5") (pin "1") (pinfunction "1_1") (pintype "passive"))
      (node (ref "U$10") (pin "9") (pinfunction "9.STR_9") (pintype "bidirectional"))
    )
    (net (code "68") (name "Net-(U$10-15.PWDN)") (class "Default")
      (node (ref "J3") (pin "1") (pinfunction "1_1") (pintype "passive"))
      (node (ref "U$10") (pin "15") (pinfunction "15.PWDN_15") (pintype "bidirectional"))
    )
    (net (code "69") (name "Net-(U$10-20.HREF)") (class "Default")
      (node (ref "J4") (pin "1") (pinfunction "1_1") (pintype "passive"))
      (node (ref "U$10") (pin "20") (pinfunction "20.HREF_20") (pintype "bidirectional"))
    )
    (net (code "70") (name "V+") (class "Default")
      (node (ref "BAT") (pin "2") (pinfunction "2_2") (pintype "passive"))
      (node (ref "U$3") (pin "3") (pinfunction "3.VBAT_3") (pintype "bidirectional"))
    )
    (net (code "71") (name "unconnected-(U$2-2.D--Pad2)") (class "Default")
      (node (ref "U$2") (pin "2") (pinfunction "2.D-_2") (pintype "bidirectional"))
    )
    (net (code "72") (name "unconnected-(U$2-3.D+-Pad3)") (class "Default")
      (node (ref "U$2") (pin "3") (pinfunction "3.D+_3") (pintype "bidirectional"))
    )
    (net (code "73") (name "unconnected-(U$2-4.1D-Pad4)") (class "Default")
      (node (ref "U$2") (pin "4") (pinfunction "4.1D_4") (pintype "bidirectional"))
    )
    (net (code "74") (name "unconnected-(U$4-4.SHDN-Pad4)") (class "Default")
      (node (ref "U$4") (pin "4") (pinfunction "4.SHDN_4") (pintype "bidirectional"))
    )
    (net (code "75") (name "unconnected-(U$7-1.RTS-Pad1)") (class "Default")
      (node (ref "U$7") (pin "1") (pinfunction "1.RTS_1") (pintype "bidirectional"))
    )
    (net (code "76") (name "unconnected-(U$7-4.5V-Pad4)") (class "Default")
      (node (ref "U$7") (pin "4") (pinfunction "4.5V_4") (pintype "bidirectional"))
    )
    (net (code "77") (name "unconnected-(U$7-5.CTS-Pad5)") (class "Default")
      (node (ref "U$7") (pin "5") (pinfunction "5.CTS_5") (pintype "bidirectional"))
    )
    (net (code "78") (name "unconnected-(U$8-7.BLK-Pad7)") (class "Default")
      (node (ref "U$8") (pin "7") (pinfunction "7.BLK_7") (pintype "bidirectional"))
    )
    (net (code "79") (name "unconnected-(U$9-11.NC-Pad11)") (class "Default")
      (node (ref "U$9") (pin "11") (pinfunction "11.NC_11") (pintype "bidirectional"))
    )
    (net (code "80") (name "unconnected-(U$9-14.NC-Pad14)") (class "Default")
      (node (ref "U$9") (pin "14") (pinfunction "14.NC_14") (pintype "bidirectional"))
    )
    (net (code "81") (name "unconnected-(U$9-19.INTB-Pad19)") (class "Default")
      (node (ref "U$9") (pin "19") (pinfunction "19.INTB_19") (pintype "bidirectional"))
    )
    (net (code "82") (name "unconnected-(U$9-20.INTA-Pad20)") (class "Default")
      (node (ref "U$9") (pin "20") (pinfunction "20.INTA_20") (pintype "bidirectional"))
    )
  )
)
